# Project_design.net
KiCad netlist of a schematic drawn in Altium Designer
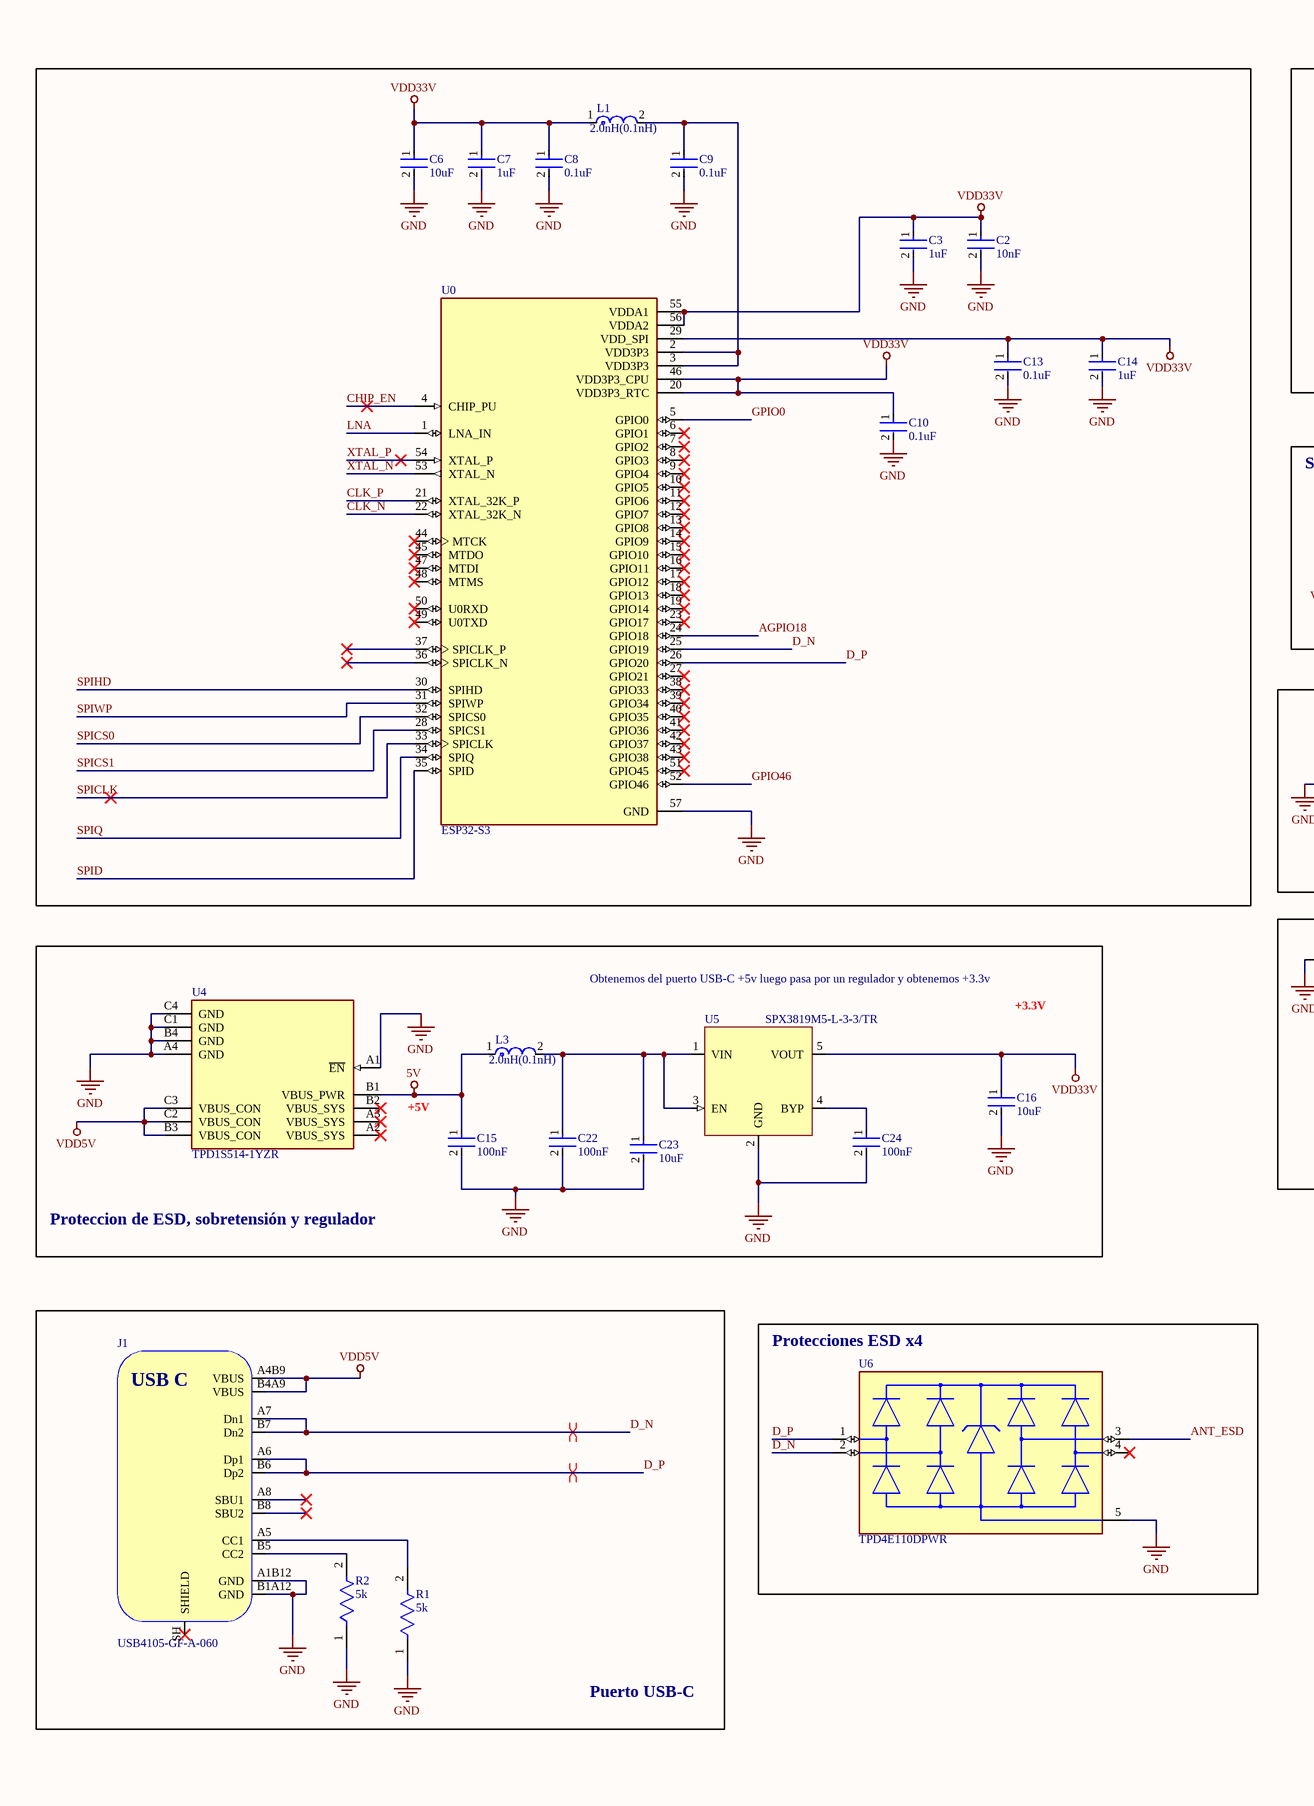
[diagram p0: Project_design.SchDoc, left]
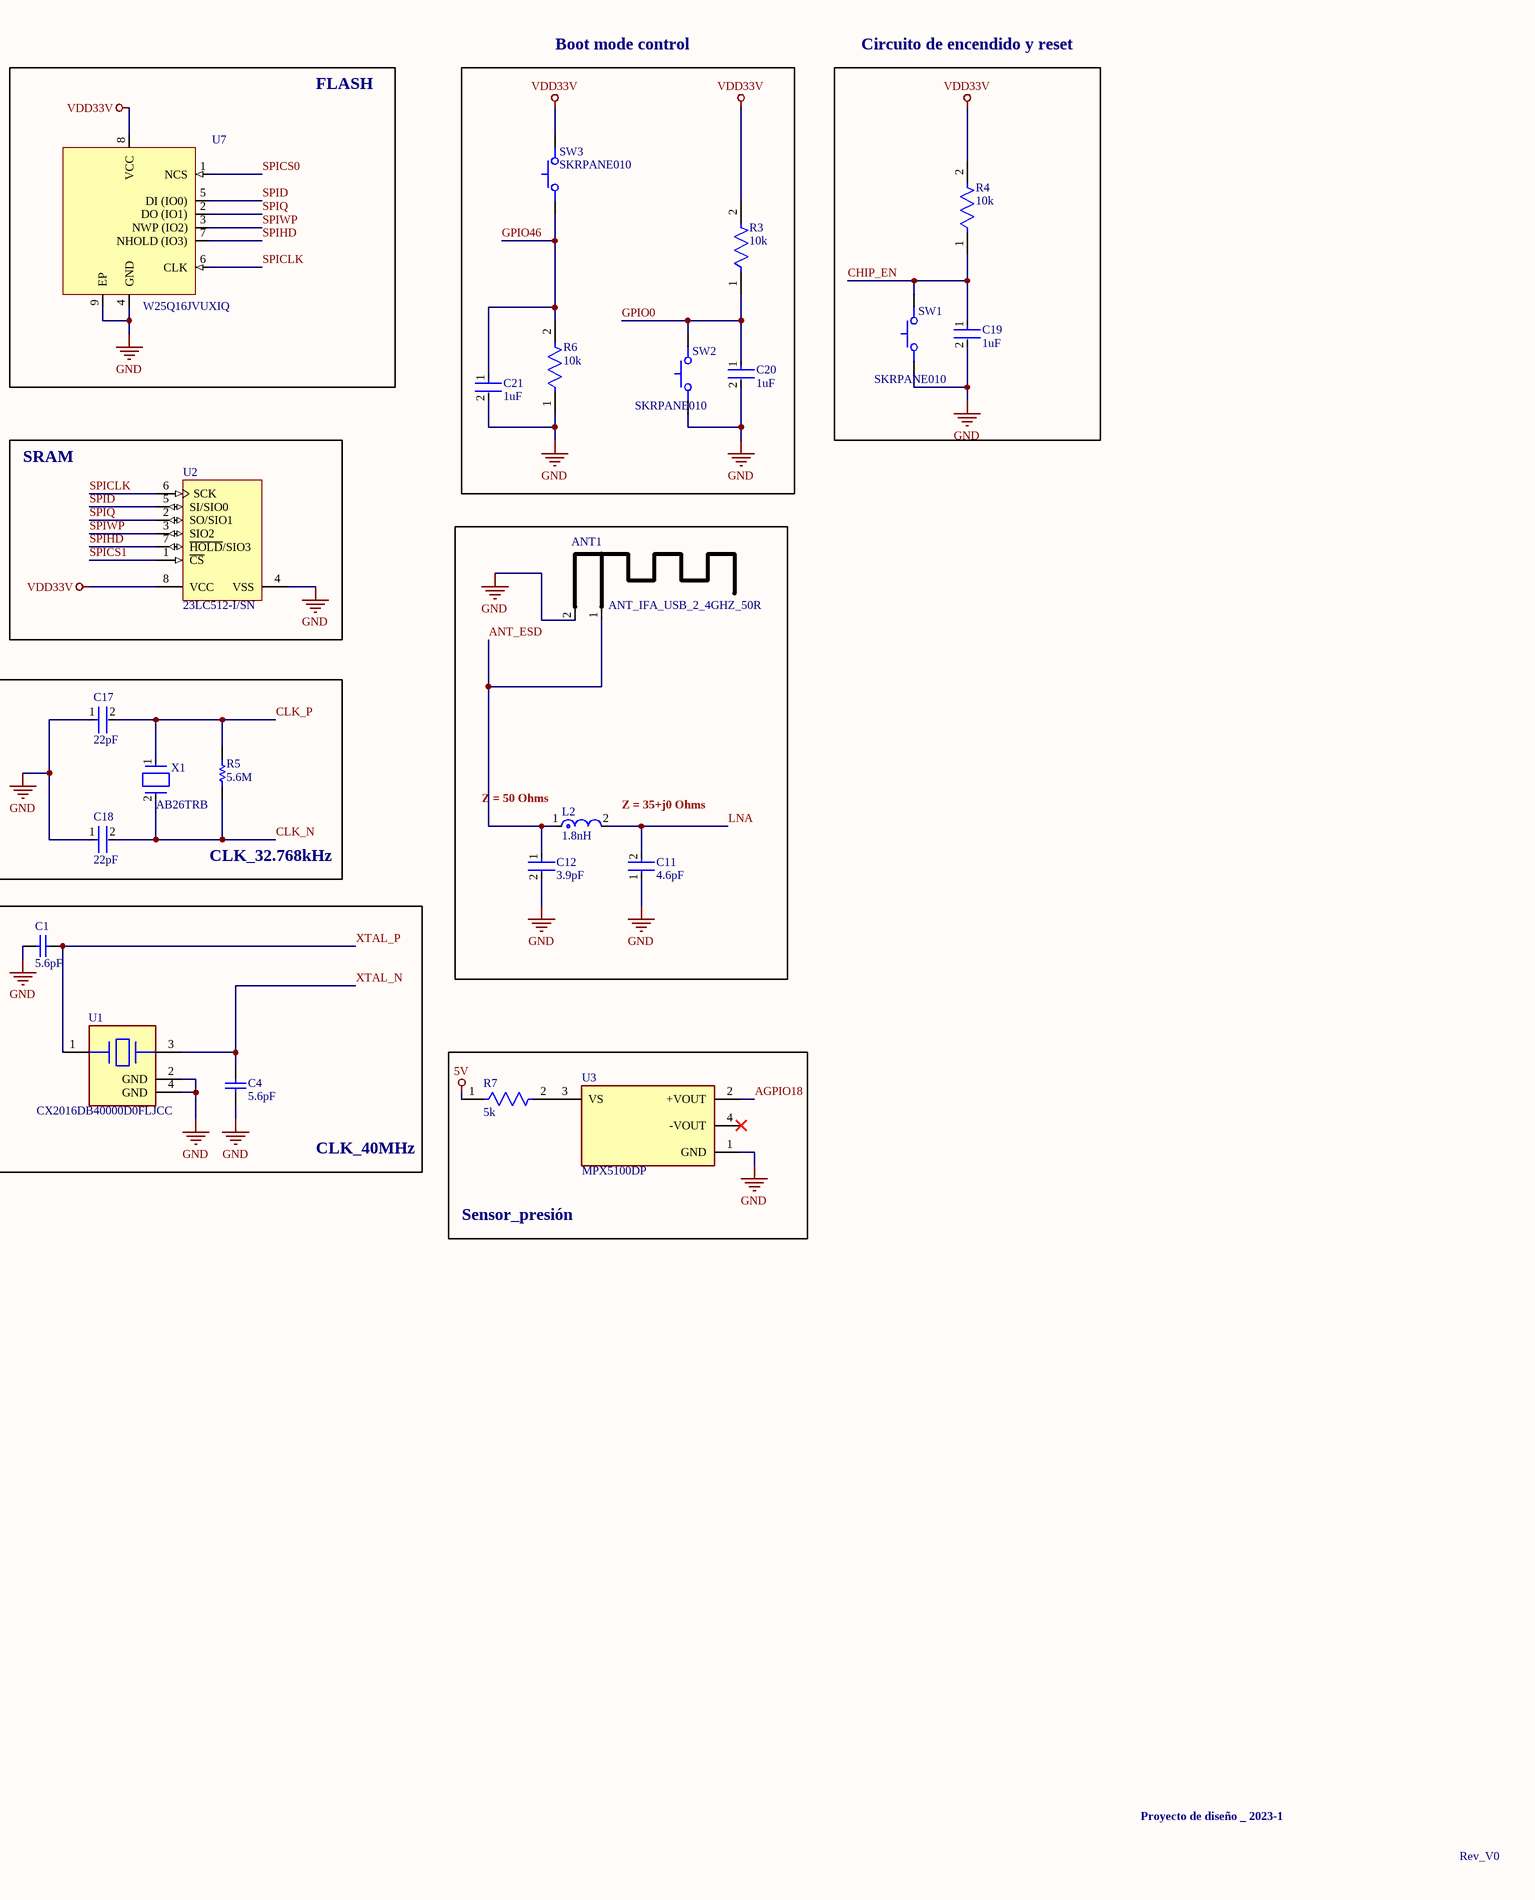
[diagram p1: Project_design.SchDoc, right]

(export (version "E")
  (design (tool "Eeschema 10.0.6"))
  (components
    (comp (ref "ANT1")
      (value "ANT_IFA_USB_2_4GHZ_50R")
      (footprint "ANT_IFA_USB_2_4GHZ_50R")
      (description "Inverted F 2.4GHz ISM PCB Antenna 50 Ohm")
      (fields (field (name "SOURCE") "Schematic-Lib-PhilsLab.SchLib"))
      (libsource (lib "Universidad Industrial de Santander") (part "ANT_IFA_USB_2_4GHZ_50R"))
    )
    (comp (ref "C1")
      (value "5.6pF")
      (footprint "CAPC1006X50X20LL10T10")
      (fields
        (field (name "MANUFACTURER") "AVX Interconnect / Elco")
        (field (name "PART NUMBER") "04023J5R6BBSTR")
      )
      (libsource (lib "Altium Content Vault") (part "CAP"))
    )
    (comp (ref "C2")
      (value "10nF")
      (footprint "FP-GRM033-0_03-IPC_B")
      (description "Chip Multilayer Ceramic Capacitors for General Purpose, 0201, 10000pF, X7R, 15%, 10%, 10V")
      (fields (field (name "VOLTAGE") "10V") (field (name "TOLERANCE") "10%"))
      (libsource (lib "Altium Content Vault") (part "b4654b650e69147ec39a6b967a45e02"))
    )
    (comp (ref "C3")
      (value "1uF")
      (footprint "FP-C0402C105K9PACTU-MFG")
      (description "CAP CER 1UF 6.3V X5R 0402")
      (fields (field (name "TOLERANCE") "10%") (field (name "VOLTAGE") "6.3V"))
      (libsource (lib "Altium Content Vault") (part "11868f565c42a9108669ba33697ecf6"))
    )
    (comp (ref "C4")
      (value "5.6pF")
      (footprint "CAPC1006X50X20LL10T10")
      (fields
        (field (name "MANUFACTURER") "AVX Interconnect / Elco")
        (field (name "PART NUMBER") "04023J5R6BBSTR")
      )
      (libsource (lib "Altium Content Vault") (part "CAP"))
    )
    (comp (ref "C6")
      (value "10uF")
      (footprint "FP-GRM155-0_2-IPC_C")
      (description "Chip Multilayer Ceramic Capacitors for General Purpose, 0402, 10uF, X5R, 15%, 20%, 6.3V")
      (libsource (lib "Altium Content Vault") (part "b4654b650e69147ec39a6b967a45e02"))
    )
    (comp (ref "C7")
      (value "1uF")
      (footprint "FP-C0402C105K9PACTU-MFG")
      (description "CAP CER 1UF 6.3V X5R 0402")
      (fields (field (name "TOLERANCE") "10%") (field (name "VOLTAGE") "6.3V"))
      (libsource (lib "Altium Content Vault") (part "11868f565c42a9108669ba33697ecf6"))
    )
    (comp (ref "C8")
      (value "0.1uF")
      (footprint "FP-CL278-IPC_C")
      (description "Cap Ceramic 100nF 25V X5R ±10% SMD 0402 +85°C Paper T/R")
      (fields (field (name "VOLTAGE") "25V") (field (name "TOLERANCE") "10%"))
      (libsource (lib "Altium Content Vault") (part "b4654b650e69147ec39a6b967a45e02"))
    )
    (comp (ref "C9")
      (value "0.1uF")
      (footprint "FP-CL278-IPC_C")
      (description "Cap Ceramic 100nF 25V X5R ±10% SMD 0402 +85°C Paper T/R")
      (fields (field (name "VOLTAGE") "25V") (field (name "TOLERANCE") "10%"))
      (libsource (lib "Altium Content Vault") (part "b4654b650e69147ec39a6b967a45e02"))
    )
    (comp (ref "C10")
      (value "0.1uF")
      (footprint "FP-CL278-IPC_C")
      (description "Cap Ceramic 100nF 25V X5R ±10% SMD 0402 +85°C Paper T/R")
      (fields (field (name "VOLTAGE") "25V") (field (name "TOLERANCE") "10%"))
      (libsource (lib "Altium Content Vault") (part "b4654b650e69147ec39a6b967a45e02"))
    )
    (comp (ref "C11")
      (value "4.6pF")
      (footprint "FP-CBR04C-MFG")
      (description "CBR0402 4.6 pF 30ppm/°C 0.1 pF C0G 50 V")
      (fields (field (name "MANUFACTURER PART NUMBER") "CBR04C469B5GAC") (field (name "TOLERANCE") "0.1 pF"))
      (libsource (lib "Altium Content Vault") (part "236180d848d6139a670b325ea6854c9"))
    )
    (comp (ref "C12")
      (value "3.9pF")
      (footprint "FP-GRM033-0_03-IPC_B")
      (description "Chip Multilayer Ceramic Capacitors for General Purpose, 0201, 3.9pF, C0G, 30ppm/°C, 0.25pF, 50V")
      (libsource (lib "Altium Content Vault") (part "b4654b650e69147ec39a6b967a45e02"))
    )
    (comp (ref "C13")
      (value "0.1uF")
      (footprint "FP-CL278-IPC_C")
      (description "Cap Ceramic 100nF 25V X5R ±10% SMD 0402 +85°C Paper T/R")
      (fields (field (name "VOLTAGE") "25V") (field (name "TOLERANCE") "10%"))
      (libsource (lib "Altium Content Vault") (part "b4654b650e69147ec39a6b967a45e02"))
    )
    (comp (ref "C14")
      (value "1uF")
      (footprint "FP-C0402C105K9PACTU-MFG")
      (description "CAP CER 1UF 6.3V X5R 0402")
      (fields (field (name "TOLERANCE") "10%") (field (name "VOLTAGE") "6.3V"))
      (libsource (lib "Altium Content Vault") (part "11868f565c42a9108669ba33697ecf6"))
    )
    (comp (ref "C15")
      (value "100nF")
      (footprint "FP-CL278-IPC_C")
      (description "Cap Ceramic 100nF 25V X5R ±10% SMD 0402 +85°C Paper T/R")
      (fields (field (name "VOLTAGE") "25V") (field (name "TOLERANCE") "10%"))
      (libsource (lib "Altium Content Vault") (part "b4654b650e69147ec39a6b967a45e02"))
    )
    (comp (ref "C16")
      (value "10uF")
      (footprint "FP-GRM155-0_2-IPC_C")
      (description "Chip Multilayer Ceramic Capacitors for General Purpose, 0402, 10uF, X5R, 15%, 20%, 6.3V")
      (libsource (lib "Altium Content Vault") (part "b4654b650e69147ec39a6b967a45e02"))
    )
    (comp (ref "C17")
      (value "22pF")
      (footprint "FP-C0603C-CF-MFG")
      (description "Cap Ceramic 22pF 50V C0G 5% SMD 0603 125°C Paper T/R")
      (fields (field (name "MANUFACTURER PART NUMBER") "C0603C220J5GACTU") (field (name "TOLERANCE") "0.05"))
      (libsource (lib "Altium Content Vault") (part "b4654b650e69147ec39a6b967a45e02"))
    )
    (comp (ref "C18")
      (value "22pF")
      (footprint "FP-C0603C-CF-MFG")
      (description "Cap Ceramic 22pF 50V C0G 5% SMD 0603 125°C Paper T/R")
      (fields (field (name "MANUFACTURER PART NUMBER") "C0603C220J5GACTU") (field (name "TOLERANCE") "0.05"))
      (libsource (lib "Altium Content Vault") (part "b4654b650e69147ec39a6b967a45e02"))
    )
    (comp (ref "C19")
      (value "1uF")
      (footprint "FP-C0402C105K9PACTU-MFG")
      (description "CAP CER 1UF 6.3V X5R 0402")
      (fields (field (name "TOLERANCE") "10%") (field (name "VOLTAGE") "6.3V"))
      (libsource (lib "Altium Content Vault") (part "11868f565c42a9108669ba33697ecf6"))
    )
    (comp (ref "C20")
      (value "1uF")
      (footprint "FP-C0402C105K9PACTU-MFG")
      (description "CAP CER 1UF 6.3V X5R 0402")
      (fields (field (name "TOLERANCE") "10%") (field (name "VOLTAGE") "6.3V"))
      (libsource (lib "Altium Content Vault") (part "11868f565c42a9108669ba33697ecf6"))
    )
    (comp (ref "C21")
      (value "1uF")
      (footprint "FP-C0402C105K9PACTU-MFG")
      (description "CAP CER 1UF 6.3V X5R 0402")
      (fields (field (name "TOLERANCE") "10%") (field (name "VOLTAGE") "6.3V"))
      (libsource (lib "Altium Content Vault") (part "11868f565c42a9108669ba33697ecf6"))
    )
    (comp (ref "C22")
      (value "100nF")
      (footprint "FP-CL278-IPC_C")
      (description "Cap Ceramic 100nF 25V X5R ±10% SMD 0402 +85°C Paper T/R")
      (fields (field (name "VOLTAGE") "25V") (field (name "TOLERANCE") "10%"))
      (libsource (lib "Altium Content Vault") (part "b4654b650e69147ec39a6b967a45e02"))
    )
    (comp (ref "C23")
      (value "10uF")
      (footprint "FP-GRM155-0_2-IPC_C")
      (description "Chip Multilayer Ceramic Capacitors for General Purpose, 0402, 10uF, X5R, 15%, 20%, 6.3V")
      (libsource (lib "Altium Content Vault") (part "b4654b650e69147ec39a6b967a45e02"))
    )
    (comp (ref "C24")
      (value "100nF")
      (footprint "FP-CL278-IPC_C")
      (description "Cap Ceramic 100nF 25V X5R ±10% SMD 0402 +85°C Paper T/R")
      (fields (field (name "VOLTAGE") "25V") (field (name "TOLERANCE") "10%"))
      (libsource (lib "Altium Content Vault") (part "b4654b650e69147ec39a6b967a45e02"))
    )
    (comp (ref "J1")
      (value "USB4105-GF-A-060")
      (footprint "USB4105-GF-A-060")
      (description "USB Connector Type C SMT 12 Pin")
      (fields (field (name "MANUFACTURER") "GCT") (field (name "SOURCE") "Schematic-Lib-PhilsLab.SchLib"))
      (libsource (lib "Universidad Industrial de Santander") (part "USB4105-GF-A-060"))
    )
    (comp (ref "L1")
      (value "2.0nH(0.1nH)")
      (footprint "FP-LQG15HH_02-MFG")
      (description "Multilayer type RF Inductor 2nH ±0.1nH 0.09Ω 900mA 0402")
      (libsource (lib "Altium Content Vault") (part "4cc4b267dca4c8e51f7102f422741d8"))
    )
    (comp (ref "L2")
      (value "1.8nH")
      (footprint "FP-LQP03TG_02-IPC_B")
      (description "Film type RF Inductor 1.8nH ±0.1nH 600mA 0.15Ω 0201 (0603)")
      (libsource (lib "Altium Content Vault") (part "4cc4b267dca4c8e51f7102f422741d8"))
    )
    (comp (ref "L3")
      (value "2.0nH(0.1nH)")
      (footprint "FP-LQG15HH_02-MFG")
      (description "Multilayer type RF Inductor 2nH ±0.1nH 0.09Ω 900mA 0402")
      (libsource (lib "Altium Content Vault") (part "4cc4b267dca4c8e51f7102f422741d8"))
    )
    (comp (ref "R1")
      (value "5k")
      (footprint "FP-PNM0402-IPC_C")
      (description "RES SMD 5K OHM 0.1% 1/20W 0402")
      (fields (field (name "TOLERANCE") "0.1%"))
      (libsource (lib "Altium Content Vault") (part "1029c3af85768c4190bb7ad29bc67b5"))
    )
    (comp (ref "R2")
      (value "5k")
      (footprint "FP-PNM0402-IPC_C")
      (description "RES SMD 5K OHM 0.1% 1/20W 0402")
      (fields (field (name "TOLERANCE") "0.1%"))
      (libsource (lib "Altium Content Vault") (part "1029c3af85768c4190bb7ad29bc67b5"))
    )
    (comp (ref "R3")
      (value "10k")
      (footprint "FP-CRGP0603-IPC_C")
      (description "CRGP 0603 10K 1%")
      (fields
        (field (name "OCTOPART") "https://octopart.com/crgp0603f10k-te+connectivity-91018721")
        (field (name "MANUFACTURER PART NUMBER") "CRGP0603F10K")
      )
      (libsource (lib "Altium Content Vault") (part "1029c3af85768c4190bb7ad29bc67b5"))
    )
    (comp (ref "R4")
      (value "10k")
      (footprint "FP-CRGP0603-IPC_C")
      (description "CRGP 0603 10K 1%")
      (fields
        (field (name "OCTOPART") "https://octopart.com/crgp0603f10k-te+connectivity-91018721")
        (field (name "MANUFACTURER PART NUMBER") "CRGP0603F10K")
      )
      (libsource (lib "Altium Content Vault") (part "1029c3af85768c4190bb7ad29bc67b5"))
    )
    (comp (ref "R5")
      (value "5.6M")
      (footprint "RESC1005X40X25ML05T10")
      (fields (field (name "MANUFACTURER") "Yageo / Phycomp") (field (name "PART NUMBER") "RC0402JR-075M6L"))
      (libsource (lib "Altium Content Vault") (part "RES"))
    )
    (comp (ref "R6")
      (value "10k")
      (footprint "FP-CRGP0603-IPC_C")
      (description "CRGP 0603 10K 1%")
      (fields
        (field (name "OCTOPART") "https://octopart.com/crgp0603f10k-te+connectivity-91018721")
        (field (name "MANUFACTURER PART NUMBER") "CRGP0603F10K")
      )
      (libsource (lib "Altium Content Vault") (part "1029c3af85768c4190bb7ad29bc67b5"))
    )
    (comp (ref "R7")
      (value "5k")
      (footprint "FP-PNM0402-IPC_C")
      (description "RES SMD 5K OHM 0.1% 1/20W 0402")
      (fields (field (name "TOLERANCE") "0.1%"))
      (libsource (lib "Altium Content Vault") (part "1029c3af85768c4190bb7ad29bc67b5"))
    )
    (comp (ref "SW1")
      (value "SKRPANE010")
      (footprint "SKRPANE010")
      (description "Tactile Switch SMD SPST")
      (fields (field (name "MANUFACTURER") "Alps Alpine"))
      (libsource (lib "Schematic-Lib-PhilsLab") (part "SKRPANE010"))
    )
    (comp (ref "SW2")
      (value "SKRPANE010")
      (footprint "SKRPANE010")
      (description "Tactile Switch SMD SPST")
      (fields (field (name "MANUFACTURER") "Alps Alpine"))
      (libsource (lib "Schematic-Lib-PhilsLab") (part "SKRPANE010"))
    )
    (comp (ref "SW3")
      (value "SKRPANE010")
      (footprint "SKRPANE010")
      (description "Tactile Switch SMD SPST")
      (fields (field (name "MANUFACTURER") "Alps Alpine"))
      (libsource (lib "Schematic-Lib-PhilsLab") (part "SKRPANE010"))
    )
    (comp (ref "U0")
      (value "ESP32-S3")
      (footprint "IC_ESP32-S3")
      (fields (field (name "MF") "Espressif Systems"))
      (libsource (lib "Universidad Industrial de Santander") (part "ESP32-S3"))
    )
    (comp (ref "U1")
      (value "CX2016DB40000D0FLJCC")
      (footprint "FP-CX2016DB-MFG")
      (description "CRYSTAL 40.0000MHZ 8PF SMD")
      (fields
        (field (name "TOLERANCE") "15ppm")
        (field (name "OCTOPART") "https://octopart.com/cx2016db40000d0fljcc-avx+%2F+kyocera-71139660")
      )
      (libsource (lib "Altium Content Vault") (part "28df8d7a1f20b35eca55ec9e48b468b"))
    )
    (comp (ref "U2")
      (value "23LC512-I/SN")
      (footprint "MCHP-SOIC-SN8_N")
      (fields (field (name "MANUFACTURER") "Microchip"))
      (libsource (lib "Altium Content Vault") (part "MCHP-23A1024_512-LC1024_512-8"))
    )
    (comp (ref "U3")
      (value "MPX5100DP")
      (footprint "FP-SOT1754-1-MFG")
      (libsource (lib "Altium Content Vault") (part "60e7d013c733a87ffd9e1aafd0260a2"))
    )
    (comp (ref "U4")
      (value "TPD1S514-1YZR")
      (footprint "BGA12N40P3X4_140X189X62N")
      (description "Interface Circuit, PBGA12")
      (fields (field (name "MF") "Texas Instruments"))
      (libsource (lib "Universidad Industrial de Santander") (part "TPD1S514-1YZR"))
    )
    (comp (ref "U5")
      (value "SPX3819M5-L-3-3/TR")
      (footprint "SOT-23-5")
      (description "500mA +3.3V Low-Noise LDO Voltage Regulator")
      (fields
        (field (name "MANUFACTURER") "MaxLinear")
        (field (name "SOURCE") "Schematic-Lib-PhilsLab.SchLib")
      )
      (libsource (lib "Universidad Industrial de Santander") (part "SPX3819M5-L-3-3/TR"))
    )
    (comp (ref "U6")
      (value "TPD4E110DPWR")
      (footprint "FP-DPW0004A-MFG")
      (description "TVS DIODE 5.5VWM 13VC 4X2SON")
      (libsource (lib "Altium Content Vault") (part "dc33b8a9bfad9debc17581ebbb18bcc"))
    )
    (comp (ref "U7")
      (value "W25Q16JVUXIQ")
      (footprint "USON-8-2X3MM")
      (description "16M-BIT SERIAL FLASH MEMORY WITH DUAL/QUAD SPI USON-8")
      (fields (field (name "MANUFACTURER") "Winbond") (field (name "SOURCE") "Schematic-Lib-PhilsLab.SchLib"))
      (libsource (lib "Universidad Industrial de Santander") (part "W25Q16JVUXIQ"))
    )
    (comp (ref "X1")
      (value "AB26TRB")
      (footprint "FP-AB26TRB-MFG")
      (description "CRYSTAL 32.7680KHZ 12.5PF TH")
      (fields (field (name "TOLERANCE") "20ppm"))
      (libsource (lib "Altium Content Vault") (part "c23a69dc6c9e2f18f2079038eb95dd1"))
    )
  )
  (nets
    (net (code "1") (name "/AGPIO18") (class "Default")
      (node (ref "U0") (pin "24") (pinfunction "GPIO18_24") (pintype "bidirectional"))
      (node (ref "U3") (pin "2") (pinfunction "+VOUT_2") (pintype "passive"))
    )
    (net (code "2") (name "/ANT_ESD") (class "Default")
      (node (ref "ANT1") (pin "1") (pinfunction "RF_1") (pintype "passive"))
      (node (ref "C12") (pin "1") (pinfunction "1_1") (pintype "passive"))
      (node (ref "L2") (pin "1") (pinfunction "1_1") (pintype "passive"))
      (node (ref "U6") (pin "3") (pinfunction "IO3_3") (pintype "bidirectional"))
    )
    (net (code "3") (name "/CHIP_EN") (class "Default")
      (node (ref "C19") (pin "1") (pinfunction "1_1") (pintype "passive"))
      (node (ref "R4") (pin "1") (pinfunction "1_1") (pintype "passive"))
      (node (ref "SW1") (pin "34") (pintype "passive"))
      (node (ref "U0") (pin "4") (pinfunction "CHIP_PU_4") (pintype "input"))
    )
    (net (code "4") (name "/CLK_N") (class "Default")
      (node (ref "C18") (pin "2") (pinfunction "2_2") (pintype "passive"))
      (node (ref "R5") (pin "1") (pinfunction "1_1") (pintype "passive"))
      (node (ref "U0") (pin "22") (pinfunction "XTAL_32K_N_22") (pintype "bidirectional"))
      (node (ref "X1") (pin "2") (pinfunction "2_2") (pintype "passive"))
    )
    (net (code "5") (name "/CLK_P") (class "Default")
      (node (ref "C17") (pin "2") (pinfunction "2_2") (pintype "passive"))
      (node (ref "R5") (pin "2") (pinfunction "2_2") (pintype "passive"))
      (node (ref "U0") (pin "21") (pinfunction "XTAL_32K_P_21") (pintype "bidirectional"))
      (node (ref "X1") (pin "1") (pinfunction "1_1") (pintype "passive"))
    )
    (net (code "6") (name "/D_N") (class "Default")
      (node (ref "J1") (pin "A7") (pinfunction "Dn1_A7") (pintype "passive"))
      (node (ref "J1") (pin "B7") (pinfunction "Dn2_B7") (pintype "passive"))
      (node (ref "U0") (pin "25") (pinfunction "GPIO19_25") (pintype "bidirectional"))
      (node (ref "U6") (pin "2") (pinfunction "IO2_2") (pintype "bidirectional"))
    )
    (net (code "7") (name "/D_P") (class "Default")
      (node (ref "J1") (pin "A6") (pinfunction "Dp1_A6") (pintype "passive"))
      (node (ref "J1") (pin "B6") (pinfunction "Dp2_B6") (pintype "passive"))
      (node (ref "U0") (pin "26") (pinfunction "GPIO20_26") (pintype "bidirectional"))
      (node (ref "U6") (pin "1") (pinfunction "IO1_1") (pintype "bidirectional"))
    )
    (net (code "8") (name "/GPIO0") (class "Default")
      (node (ref "C20") (pin "1") (pinfunction "1_1") (pintype "passive"))
      (node (ref "R3") (pin "1") (pinfunction "1_1") (pintype "passive"))
      (node (ref "SW2") (pin "34") (pintype "passive"))
      (node (ref "U0") (pin "5") (pinfunction "GPIO0_5") (pintype "bidirectional"))
    )
    (net (code "9") (name "/GPIO46") (class "Default")
      (node (ref "C21") (pin "1") (pinfunction "1_1") (pintype "passive"))
      (node (ref "R6") (pin "2") (pinfunction "2_2") (pintype "passive"))
      (node (ref "SW3") (pin "12") (pintype "passive"))
      (node (ref "U0") (pin "52") (pinfunction "GPIO46_52") (pintype "bidirectional"))
    )
    (net (code "10") (name "/LNA") (class "Default")
      (node (ref "C11") (pin "2") (pinfunction "2_2") (pintype "passive"))
      (node (ref "L2") (pin "2") (pinfunction "2_2") (pintype "passive"))
      (node (ref "U0") (pin "1") (pinfunction "LNA_IN_1") (pintype "bidirectional"))
    )
    (net (code "11") (name "/SPICLK") (class "Default")
      (node (ref "U0") (pin "33") (pinfunction "SPICLK_33") (pintype "bidirectional"))
      (node (ref "U2") (pin "6") (pinfunction "SCK_6") (pintype "input"))
      (node (ref "U7") (pin "6") (pinfunction "CLK_6") (pintype "input"))
    )
    (net (code "12") (name "/SPICS0") (class "Default")
      (node (ref "U0") (pin "32") (pinfunction "SPICS0_32") (pintype "bidirectional"))
      (node (ref "U7") (pin "1") (pinfunction "NCS_1") (pintype "input"))
    )
    (net (code "13") (name "/SPICS1") (class "Default")
      (node (ref "U0") (pin "28") (pinfunction "SPICS1_28") (pintype "bidirectional"))
      (node (ref "U2") (pin "1") (pinfunction "~{CS}_1") (pintype "input"))
    )
    (net (code "14") (name "/SPID") (class "Default")
      (node (ref "U0") (pin "35") (pinfunction "SPID_35") (pintype "bidirectional"))
      (node (ref "U2") (pin "5") (pinfunction "SI/SIO0_5") (pintype "bidirectional"))
      (node (ref "U7") (pin "5") (pinfunction "DI_(IO0)_5") (pintype "bidirectional"))
    )
    (net (code "15") (name "/SPIHD") (class "Default")
      (node (ref "U0") (pin "30") (pinfunction "SPIHD_30") (pintype "bidirectional"))
      (node (ref "U2") (pin "7") (pinfunction "~{HOLD}/SIO3_7") (pintype "bidirectional"))
      (node (ref "U7") (pin "7") (pinfunction "NHOLD_(IO3)_7") (pintype "bidirectional"))
    )
    (net (code "16") (name "/SPIQ") (class "Default")
      (node (ref "U0") (pin "34") (pinfunction "SPIQ_34") (pintype "bidirectional"))
      (node (ref "U2") (pin "2") (pinfunction "SO/SIO1_2") (pintype "bidirectional"))
      (node (ref "U7") (pin "2") (pinfunction "DO_(IO1)_2") (pintype "bidirectional"))
    )
    (net (code "17") (name "/SPIWP") (class "Default")
      (node (ref "U0") (pin "31") (pinfunction "SPIWP_31") (pintype "bidirectional"))
      (node (ref "U2") (pin "3") (pinfunction "SIO2_3") (pintype "bidirectional"))
      (node (ref "U7") (pin "3") (pinfunction "NWP_(IO2)_3") (pintype "bidirectional"))
    )
    (net (code "18") (name "/XTAL_N") (class "Default")
      (node (ref "C4") (pin "2") (pinfunction "2_2") (pintype "passive"))
      (node (ref "U0") (pin "53") (pinfunction "XTAL_N_53") (pintype "output"))
      (node (ref "U1") (pin "3") (pinfunction "3_3") (pintype "passive"))
    )
    (net (code "19") (name "/XTAL_P") (class "Default")
      (node (ref "C1") (pin "2") (pinfunction "2_2") (pintype "passive"))
      (node (ref "U0") (pin "54") (pinfunction "XTAL_P_54") (pintype "input"))
      (node (ref "U1") (pin "1") (pinfunction "1_1") (pintype "passive"))
    )
    (net (code "20") (name "5V") (class "Default")
      (node (ref "C15") (pin "1") (pinfunction "1_1") (pintype "passive"))
      (node (ref "L3") (pin "1") (pinfunction "1_1") (pintype "passive"))
      (node (ref "R7") (pin "1") (pinfunction "1_1") (pintype "passive"))
      (node (ref "U4") (pin "B1") (pinfunction "VBUS_PWR_B1") (pintype "power_in"))
    )
    (net (code "21") (name "GND") (class "Default")
      (node (ref "ANT1") (pin "2") (pinfunction "GND_2") (pintype "passive"))
      (node (ref "C1") (pin "1") (pinfunction "1_1") (pintype "passive"))
      (node (ref "C10") (pin "2") (pinfunction "2_2") (pintype "passive"))
      (node (ref "C11") (pin "1") (pinfunction "1_1") (pintype "passive"))
      (node (ref "C12") (pin "2") (pinfunction "2_2") (pintype "passive"))
      (node (ref "C13") (pin "2") (pinfunction "2_2") (pintype "passive"))
      (node (ref "C14") (pin "2") (pinfunction "2_2") (pintype "passive"))
      (node (ref "C15") (pin "2") (pinfunction "2_2") (pintype "passive"))
      (node (ref "C16") (pin "2") (pinfunction "2_2") (pintype "passive"))
      (node (ref "C17") (pin "1") (pinfunction "1_1") (pintype "passive"))
      (node (ref "C18") (pin "1") (pinfunction "1_1") (pintype "passive"))
      (node (ref "C19") (pin "2") (pinfunction "2_2") (pintype "passive"))
      (node (ref "C2") (pin "2") (pinfunction "2_2") (pintype "passive"))
      (node (ref "C20") (pin "2") (pinfunction "2_2") (pintype "passive"))
      (node (ref "C21") (pin "2") (pinfunction "2_2") (pintype "passive"))
      (node (ref "C22") (pin "2") (pinfunction "2_2") (pintype "passive"))
      (node (ref "C23") (pin "2") (pinfunction "2_2") (pintype "passive"))
      (node (ref "C24") (pin "2") (pinfunction "2_2") (pintype "passive"))
      (node (ref "C3") (pin "2") (pinfunction "2_2") (pintype "passive"))
      (node (ref "C4") (pin "1") (pinfunction "1_1") (pintype "passive"))
      (node (ref "C6") (pin "2") (pinfunction "2_2") (pintype "passive"))
      (node (ref "C7") (pin "2") (pinfunction "2_2") (pintype "passive"))
      (node (ref "C8") (pin "2") (pinfunction "2_2") (pintype "passive"))
      (node (ref "C9") (pin "2") (pinfunction "2_2") (pintype "passive"))
      (node (ref "J1") (pin "A1B12") (pinfunction "GND_A1B12") (pintype "passive"))
      (node (ref "J1") (pin "B1A12") (pinfunction "GND_B1A12") (pintype "passive"))
      (node (ref "R1") (pin "1") (pinfunction "1_1") (pintype "passive"))
      (node (ref "R2") (pin "1") (pinfunction "1_1") (pintype "passive"))
      (node (ref "R6") (pin "1") (pinfunction "1_1") (pintype "passive"))
      (node (ref "SW1") (pin "12") (pintype "passive"))
      (node (ref "SW2") (pin "12") (pintype "passive"))
      (node (ref "U0") (pin "57") (pinfunction "GND_57") (pintype "power_in"))
      (node (ref "U1") (pin "2") (pinfunction "GND_2") (pintype "power_in"))
      (node (ref "U1") (pin "4") (pinfunction "GND_4") (pintype "power_in"))
      (node (ref "U2") (pin "4") (pinfunction "VSS_4") (pintype "power_in"))
      (node (ref "U3") (pin "1") (pinfunction "GND_1") (pintype "power_in"))
      (node (ref "U4") (pin "A1") (pinfunction "~{EN}_A1") (pintype "input"))
      (node (ref "U4") (pin "A4") (pinfunction "GND_A4") (pintype "power_in"))
      (node (ref "U4") (pin "B4") (pinfunction "GND_B4") (pintype "power_in"))
      (node (ref "U4") (pin "C1") (pinfunction "GND_C1") (pintype "power_in"))
      (node (ref "U4") (pin "C4") (pinfunction "GND_C4") (pintype "power_in"))
      (node (ref "U5") (pin "2") (pinfunction "GND_2") (pintype "power_in"))
      (node (ref "U6") (pin "5") (pinfunction "GND_5") (pintype "power_in"))
      (node (ref "U7") (pin "4") (pinfunction "GND_4") (pintype "power_in"))
      (node (ref "U7") (pin "9") (pinfunction "EP_9") (pintype "power_in"))
    )
    (net (code "22") (name "Net-(C9-Pad1)") (class "Default")
      (node (ref "C9") (pin "1") (pinfunction "1_1") (pintype "passive"))
      (node (ref "L1") (pin "2") (pinfunction "2_2") (pintype "passive"))
      (node (ref "U0") (pin "2") (pinfunction "VDD3P3_2") (pintype "power_in"))
      (node (ref "U0") (pin "3") (pinfunction "VDD3P3_3") (pintype "power_in"))
    )
    (net (code "23") (name "Net-(J1-CC1)") (class "Default")
      (node (ref "J1") (pin "A5") (pinfunction "CC1_A5") (pintype "passive"))
      (node (ref "R1") (pin "2") (pinfunction "2_2") (pintype "passive"))
    )
    (net (code "24") (name "Net-(J1-CC2)") (class "Default")
      (node (ref "J1") (pin "B5") (pinfunction "CC2_B5") (pintype "passive"))
      (node (ref "R2") (pin "2") (pinfunction "2_2") (pintype "passive"))
    )
    (net (code "25") (name "Net-(U3-VS)") (class "Default")
      (node (ref "R7") (pin "2") (pinfunction "2_2") (pintype "passive"))
      (node (ref "U3") (pin "3") (pinfunction "VS_3") (pintype "power_in"))
    )
    (net (code "26") (name "Net-(U5-BYP)") (class "Default")
      (node (ref "C24") (pin "1") (pinfunction "1_1") (pintype "passive"))
      (node (ref "U5") (pin "4") (pinfunction "BYP_4") (pintype "passive"))
    )
    (net (code "27") (name "Net-(U5-EN)") (class "Default")
      (node (ref "C22") (pin "1") (pinfunction "1_1") (pintype "passive"))
      (node (ref "C23") (pin "1") (pinfunction "1_1") (pintype "passive"))
      (node (ref "L3") (pin "2") (pinfunction "2_2") (pintype "passive"))
      (node (ref "U5") (pin "1") (pinfunction "VIN_1") (pintype "power_in"))
      (node (ref "U5") (pin "3") (pinfunction "EN_3") (pintype "input"))
    )
    (net (code "28") (name "VDD5V") (class "Default")
      (node (ref "J1") (pin "A4B9") (pinfunction "VBUS_A4B9") (pintype "passive"))
      (node (ref "J1") (pin "B4A9") (pinfunction "VBUS_B4A9") (pintype "passive"))
      (node (ref "U4") (pin "B3") (pinfunction "VBUS_CON_B3") (pintype "power_in"))
      (node (ref "U4") (pin "C2") (pinfunction "VBUS_CON_C2") (pintype "power_in"))
      (node (ref "U4") (pin "C3") (pinfunction "VBUS_CON_C3") (pintype "power_in"))
    )
    (net (code "29") (name "VDD33V") (class "Default")
      (node (ref "C10") (pin "1") (pinfunction "1_1") (pintype "passive"))
      (node (ref "C13") (pin "1") (pinfunction "1_1") (pintype "passive"))
      (node (ref "C14") (pin "1") (pinfunction "1_1") (pintype "passive"))
      (node (ref "C16") (pin "1") (pinfunction "1_1") (pintype "passive"))
      (node (ref "C2") (pin "1") (pinfunction "1_1") (pintype "passive"))
      (node (ref "C3") (pin "1") (pinfunction "1_1") (pintype "passive"))
      (node (ref "C6") (pin "1") (pinfunction "1_1") (pintype "passive"))
      (node (ref "C7") (pin "1") (pinfunction "1_1") (pintype "passive"))
      (node (ref "C8") (pin "1") (pinfunction "1_1") (pintype "passive"))
      (node (ref "L1") (pin "1") (pinfunction "1_1") (pintype "passive"))
      (node (ref "R3") (pin "2") (pinfunction "2_2") (pintype "passive"))
      (node (ref "R4") (pin "2") (pinfunction "2_2") (pintype "passive"))
      (node (ref "SW3") (pin "34") (pintype "passive"))
      (node (ref "U0") (pin "20") (pinfunction "VDD3P3_RTC_20") (pintype "power_in"))
      (node (ref "U0") (pin "29") (pinfunction "VDD_SPI_29") (pintype "power_in"))
      (node (ref "U0") (pin "46") (pinfunction "VDD3P3_CPU_46") (pintype "power_in"))
      (node (ref "U0") (pin "55") (pinfunction "VDDA1_55") (pintype "power_in"))
      (node (ref "U0") (pin "56") (pinfunction "VDDA2_56") (pintype "power_in"))
      (node (ref "U2") (pin "8") (pinfunction "VCC_8") (pintype "power_in"))
      (node (ref "U5") (pin "5") (pinfunction "VOUT_5") (pintype "power_in"))
      (node (ref "U7") (pin "8") (pinfunction "VCC_8") (pintype "power_in"))
    )
    (net (code "30") (name "unconnected-(J1-SBU1-PadA8)") (class "Default")
      (node (ref "J1") (pin "A8") (pinfunction "SBU1_A8") (pintype "passive+no_connect"))
    )
    (net (code "31") (name "unconnected-(J1-SBU2-PadB8)") (class "Default")
      (node (ref "J1") (pin "B8") (pinfunction "SBU2_B8") (pintype "passive+no_connect"))
    )
    (net (code "32") (name "unconnected-(J1-SHIELD-PadSH)") (class "Default")
      (node (ref "J1") (pin "SH") (pinfunction "SHIELD_SH") (pintype "passive+no_connect"))
    )
    (net (code "33") (name "unconnected-(U0-GPIO1-Pad6)") (class "Default")
      (node (ref "U0") (pin "6") (pinfunction "GPIO1_6") (pintype "bidirectional+no_connect"))
    )
    (net (code "34") (name "unconnected-(U0-GPIO2-Pad7)") (class "Default")
      (node (ref "U0") (pin "7") (pinfunction "GPIO2_7") (pintype "bidirectional+no_connect"))
    )
    (net (code "35") (name "unconnected-(U0-GPIO3-Pad8)") (class "Default")
      (node (ref "U0") (pin "8") (pinfunction "GPIO3_8") (pintype "bidirectional+no_connect"))
    )
    (net (code "36") (name "unconnected-(U0-GPIO4-Pad9)") (class "Default")
      (node (ref "U0") (pin "9") (pinfunction "GPIO4_9") (pintype "bidirectional+no_connect"))
    )
    (net (code "37") (name "unconnected-(U0-GPIO5-Pad10)") (class "Default")
      (node (ref "U0") (pin "10") (pinfunction "GPIO5_10") (pintype "bidirectional+no_connect"))
    )
    (net (code "38") (name "unconnected-(U0-GPIO6-Pad11)") (class "Default")
      (node (ref "U0") (pin "11") (pinfunction "GPIO6_11") (pintype "bidirectional+no_connect"))
    )
    (net (code "39") (name "unconnected-(U0-GPIO7-Pad12)") (class "Default")
      (node (ref "U0") (pin "12") (pinfunction "GPIO7_12") (pintype "bidirectional+no_connect"))
    )
    (net (code "40") (name "unconnected-(U0-GPIO8-Pad13)") (class "Default")
      (node (ref "U0") (pin "13") (pinfunction "GPIO8_13") (pintype "bidirectional+no_connect"))
    )
    (net (code "41") (name "unconnected-(U0-GPIO9-Pad14)") (class "Default")
      (node (ref "U0") (pin "14") (pinfunction "GPIO9_14") (pintype "bidirectional+no_connect"))
    )
    (net (code "42") (name "unconnected-(U0-GPIO10-Pad15)") (class "Default")
      (node (ref "U0") (pin "15") (pinfunction "GPIO10_15") (pintype "bidirectional+no_connect"))
    )
    (net (code "43") (name "unconnected-(U0-GPIO11-Pad16)") (class "Default")
      (node (ref "U0") (pin "16") (pinfunction "GPIO11_16") (pintype "bidirectional+no_connect"))
    )
    (net (code "44") (name "unconnected-(U0-GPIO12-Pad17)") (class "Default")
      (node (ref "U0") (pin "17") (pinfunction "GPIO12_17") (pintype "bidirectional+no_connect"))
    )
    (net (code "45") (name "unconnected-(U0-GPIO13-Pad18)") (class "Default")
      (node (ref "U0") (pin "18") (pinfunction "GPIO13_18") (pintype "bidirectional+no_connect"))
    )
    (net (code "46") (name "unconnected-(U0-GPIO14-Pad19)") (class "Default")
      (node (ref "U0") (pin "19") (pinfunction "GPIO14_19") (pintype "bidirectional+no_connect"))
    )
    (net (code "47") (name "unconnected-(U0-GPIO17-Pad23)") (class "Default")
      (node (ref "U0") (pin "23") (pinfunction "GPIO17_23") (pintype "bidirectional+no_connect"))
    )
    (net (code "48") (name "unconnected-(U0-GPIO21-Pad27)") (class "Default")
      (node (ref "U0") (pin "27") (pinfunction "GPIO21_27") (pintype "bidirectional+no_connect"))
    )
    (net (code "49") (name "unconnected-(U0-GPIO33-Pad38)") (class "Default")
      (node (ref "U0") (pin "38") (pinfunction "GPIO33_38") (pintype "bidirectional+no_connect"))
    )
    (net (code "50") (name "unconnected-(U0-GPIO34-Pad39)") (class "Default")
      (node (ref "U0") (pin "39") (pinfunction "GPIO34_39") (pintype "bidirectional+no_connect"))
    )
    (net (code "51") (name "unconnected-(U0-GPIO35-Pad40)") (class "Default")
      (node (ref "U0") (pin "40") (pinfunction "GPIO35_40") (pintype "bidirectional+no_connect"))
    )
    (net (code "52") (name "unconnected-(U0-GPIO36-Pad41)") (class "Default")
      (node (ref "U0") (pin "41") (pinfunction "GPIO36_41") (pintype "bidirectional+no_connect"))
    )
    (net (code "53") (name "unconnected-(U0-GPIO37-Pad42)") (class "Default")
      (node (ref "U0") (pin "42") (pinfunction "GPIO37_42") (pintype "bidirectional+no_connect"))
    )
    (net (code "54") (name "unconnected-(U0-GPIO38-Pad43)") (class "Default")
      (node (ref "U0") (pin "43") (pinfunction "GPIO38_43") (pintype "bidirectional+no_connect"))
    )
    (net (code "55") (name "unconnected-(U0-GPIO45-Pad51)") (class "Default")
      (node (ref "U0") (pin "51") (pinfunction "GPIO45_51") (pintype "bidirectional+no_connect"))
    )
    (net (code "56") (name "unconnected-(U0-MTCK-Pad44)") (class "Default")
      (node (ref "U0") (pin "44") (pinfunction "MTCK_44") (pintype "bidirectional+no_connect"))
    )
    (net (code "57") (name "unconnected-(U0-MTDI-Pad47)") (class "Default")
      (node (ref "U0") (pin "47") (pinfunction "MTDI_47") (pintype "bidirectional+no_connect"))
    )
    (net (code "58") (name "unconnected-(U0-MTDO-Pad45)") (class "Default")
      (node (ref "U0") (pin "45") (pinfunction "MTDO_45") (pintype "bidirectional+no_connect"))
    )
    (net (code "59") (name "unconnected-(U0-MTMS-Pad48)") (class "Default")
      (node (ref "U0") (pin "48") (pinfunction "MTMS_48") (pintype "bidirectional+no_connect"))
    )
    (net (code "60") (name "unconnected-(U0-SPICLK_N-Pad36)") (class "Default")
      (node (ref "U0") (pin "36") (pinfunction "SPICLK_N_36") (pintype "bidirectional+no_connect"))
    )
    (net (code "61") (name "unconnected-(U0-SPICLK_P-Pad37)") (class "Default")
      (node (ref "U0") (pin "37") (pinfunction "SPICLK_P_37") (pintype "bidirectional+no_connect"))
    )
    (net (code "62") (name "unconnected-(U0-U0RXD-Pad50)") (class "Default")
      (node (ref "U0") (pin "50") (pinfunction "U0RXD_50") (pintype "bidirectional+no_connect"))
    )
    (net (code "63") (name "unconnected-(U0-U0TXD-Pad49)") (class "Default")
      (node (ref "U0") (pin "49") (pinfunction "U0TXD_49") (pintype "bidirectional+no_connect"))
    )
    (net (code "64") (name "unconnected-(U3--VOUT-Pad4)") (class "Default")
      (node (ref "U3") (pin "4") (pinfunction "-VOUT_4") (pintype "passive+no_connect"))
    )
    (net (code "65") (name "unconnected-(U4-VBUS_SYS-PadA2)") (class "Default")
      (node (ref "U4") (pin "A2") (pinfunction "VBUS_SYS_A2") (pintype "power_in+no_connect"))
    )
    (net (code "66") (name "unconnected-(U4-VBUS_SYS-PadA3)") (class "Default")
      (node (ref "U4") (pin "A3") (pinfunction "VBUS_SYS_A3") (pintype "power_in+no_connect"))
    )
    (net (code "67") (name "unconnected-(U4-VBUS_SYS-PadB2)") (class "Default")
      (node (ref "U4") (pin "B2") (pinfunction "VBUS_SYS_B2") (pintype "power_in+no_connect"))
    )
    (net (code "68") (name "unconnected-(U6-IO4-Pad4)") (class "Default")
      (node (ref "U6") (pin "4") (pinfunction "IO4_4") (pintype "bidirectional+no_connect"))
    )
  )
)
